# wordclock_v1_8.net
KiCad netlist of a schematic drawn in EAGLE
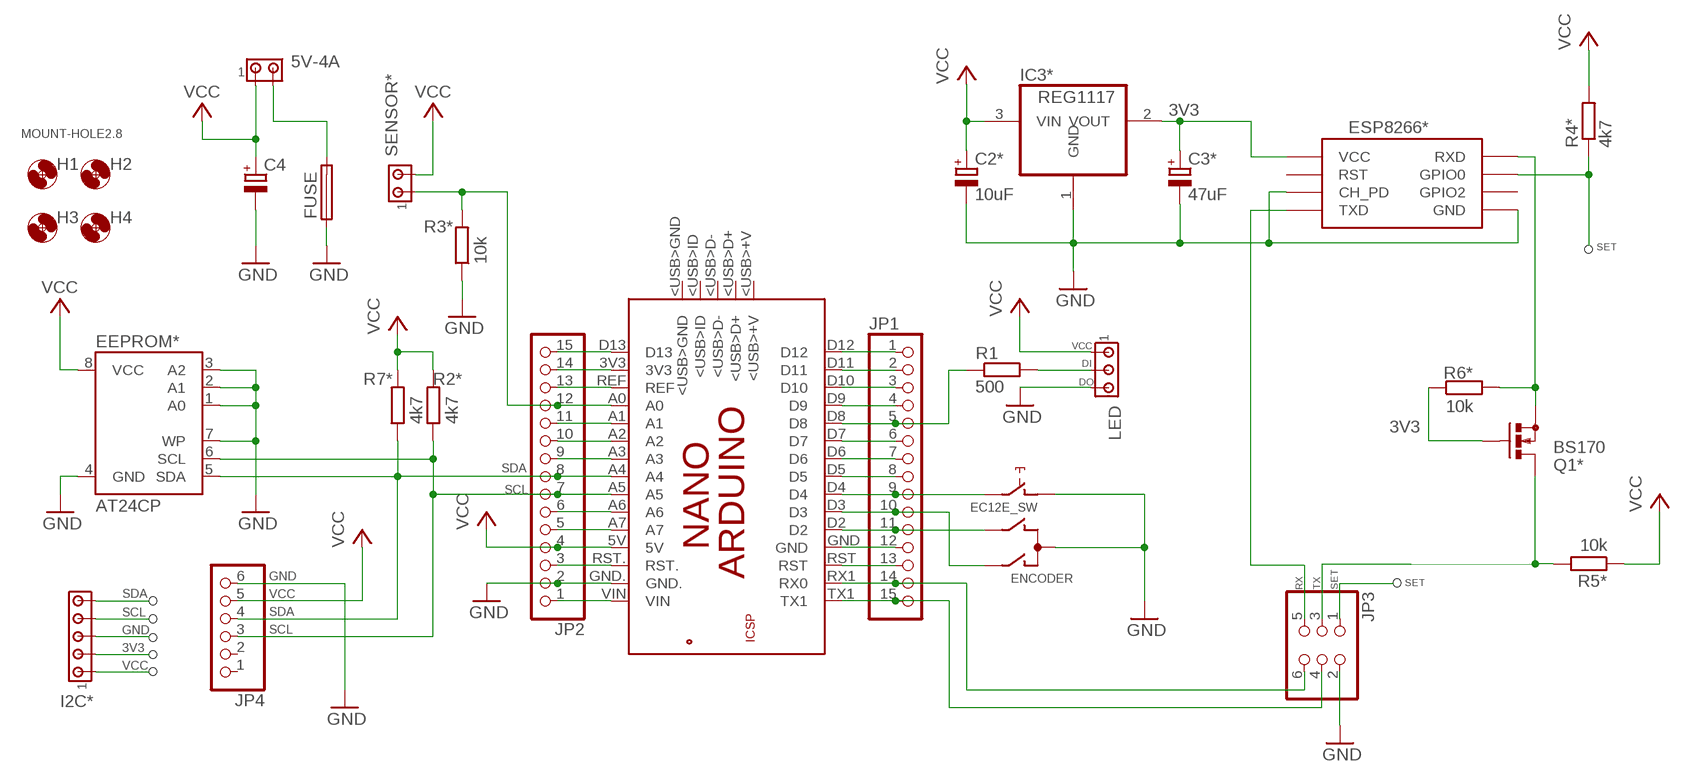
[diagram p0: schematic, sheet 1]

(export (version "E")
  (design (tool "Eeschema 10.0.6"))
  (components
    (comp (ref "5V-4A")
      (value "5V-4A")
      (footprint "eagle-import:1X2MTA")
      (libsource (lib "eagle-import") (part "MTA02-156"))
    )
    (comp (ref "C2*")
      (value "10uF")
      (footprint "eagle-import:B45181A")
      (libsource (lib "eagle-import") (part "CPOL-EUB45181A"))
    )
    (comp (ref "C3*")
      (value "47uF")
      (footprint "eagle-import:B45181A")
      (libsource (lib "eagle-import") (part "CPOL-EUB45181A"))
    )
    (comp (ref "C4")
      (value "CPOL-EUE5-10.5")
      (footprint "eagle-import:E5-10,5")
      (libsource (lib "eagle-import") (part "CPOL-EUE5-10.5"))
    )
    (comp (ref "EEPROM*")
      (value "AT24CP")
      (footprint "eagle-import:DIL08")
      (fields (field (name "MPN") "AT24C1024BW-SH-B"))
      (libsource (lib "eagle-import") (part "AT24CP"))
    )
    (comp (ref "ENCODER")
      (value "EC12E_SW")
      (footprint "eagle-import:ALPS_EC12E_SW")
      (fields (field (name "MPN") "EC12E2424407"))
      (libsource (lib "eagle-import") (part "EC12E_SW"))
    )
    (comp (ref "ESP8266*")
      (value "ESP01")
      (footprint "eagle-import:ESP01")
      (libsource (lib "eagle-import") (part "ESP01"))
    )
    (comp (ref "FUSE")
      (value "FUSELITTLEFUSE")
      (footprint "eagle-import:LITTLEFUSE")
      (libsource (lib "eagle-import") (part "FUSELITTLEFUSE"))
    )
    (comp (ref "H1")
      (value "MOUNT-HOLE2.8")
      (footprint "eagle-import:2,8")
      (libsource (lib "eagle-import") (part "MOUNT-HOLE2.8"))
    )
    (comp (ref "H2")
      (value "MOUNT-HOLE2.8")
      (footprint "eagle-import:2,8")
      (libsource (lib "eagle-import") (part "MOUNT-HOLE2.8"))
    )
    (comp (ref "H3")
      (value "MOUNT-HOLE2.8")
      (footprint "eagle-import:2,8")
      (libsource (lib "eagle-import") (part "MOUNT-HOLE2.8"))
    )
    (comp (ref "H4")
      (value "MOUNT-HOLE2.8")
      (footprint "eagle-import:2,8")
      (libsource (lib "eagle-import") (part "MOUNT-HOLE2.8"))
    )
    (comp (ref "I2C*")
      (value "MTA05-100")
      (footprint "eagle-import:10X05MTA")
      (libsource (lib "eagle-import") (part "MTA05-100"))
    )
    (comp (ref "IC3*")
      (value "REG1117")
      (footprint "eagle-import:SOT223")
      (libsource (lib "eagle-import") (part "REG1117"))
    )
    (comp (ref "JP1")
      (value "PINHD-1X15")
      (footprint "eagle-import:1X15")
      (libsource (lib "eagle-import") (part "PINHD-1X15"))
    )
    (comp (ref "JP2")
      (value "PINHD-1X15")
      (footprint "eagle-import:1X15")
      (libsource (lib "eagle-import") (part "PINHD-1X15"))
    )
    (comp (ref "JP3")
      (value "PINHD-2X3")
      (footprint "eagle-import:2X03")
      (libsource (lib "eagle-import") (part "PINHD-2X3"))
    )
    (comp (ref "JP4")
      (value "PINHD-1X6")
      (footprint "eagle-import:1X06")
      (libsource (lib "eagle-import") (part "PINHD-1X6"))
    )
    (comp (ref "LED")
      (value "MTA03-156")
      (footprint "eagle-import:1X3MTA")
      (libsource (lib "eagle-import") (part "MTA03-156"))
    )
    (comp (ref "PCB2")
      (value "ARDUINO_NANO")
      (footprint "eagle-import:ARDUINO_NANO")
      (libsource (lib "eagle-import") (part "ARDUINO_NANO"))
    )
    (comp (ref "Q1*")
      (value "BS170")
      (footprint "eagle-import:SOT54E")
      (libsource (lib "eagle-import") (part "BS170"))
    )
    (comp (ref "R1")
      (value "500")
      (footprint "eagle-import:0207_7")
      (libsource (lib "eagle-import") (part "resistor_R-EU_0207/7"))
    )
    (comp (ref "R2*")
      (value "4k7")
      (footprint "eagle-import:0207_10")
      (libsource (lib "eagle-import") (part "R-EU_0207/10"))
    )
    (comp (ref "R3*")
      (value "10k")
      (footprint "eagle-import:0207_10")
      (libsource (lib "eagle-import") (part "R-EU_0207/10"))
    )
    (comp (ref "R4*")
      (value "4k7")
      (footprint "eagle-import:0207_10")
      (libsource (lib "eagle-import") (part "R-EU_0207/10"))
    )
    (comp (ref "R5*")
      (value "10k")
      (footprint "eagle-import:0207_10")
      (libsource (lib "eagle-import") (part "R-EU_0207/10"))
    )
    (comp (ref "R6*")
      (value "10k")
      (footprint "eagle-import:0207_10")
      (libsource (lib "eagle-import") (part "R-EU_0207/10"))
    )
    (comp (ref "R7*")
      (value "4k7")
      (footprint "eagle-import:0207_10")
      (libsource (lib "eagle-import") (part "R-EU_0207/10"))
    )
    (comp (ref "SENSOR*")
      (value "MTA02-156")
      (footprint "eagle-import:1X2MTA")
      (libsource (lib "eagle-import") (part "MTA02-156"))
    )
  )
  (nets
    (net (code "1") (name "3V3") (class "Default")
      (node (ref "C3*") (pin "+") (pinfunction "+_+") (pintype "passive"))
      (node (ref "ESP8266*") (pin "VCC") (pinfunction "VCC_VCC") (pintype "bidirectional"))
      (node (ref "I2C*") (pin "2") (pinfunction "2_2") (pintype "passive"))
      (node (ref "IC3*") (pin "2") (pinfunction "VOUT_2") (pintype "output"))
      (node (ref "Q1*") (pin "G") (pinfunction "G_G") (pintype "passive"))
      (node (ref "R6*") (pin "1") (pinfunction "1_1") (pintype "passive"))
    )
    (net (code "2") (name "DI") (class "Default")
      (node (ref "LED") (pin "2") (pinfunction "2_2") (pintype "passive"))
      (node (ref "R1") (pin "2") (pinfunction "2_2") (pintype "passive"))
    )
    (net (code "3") (name "GND") (class "Default")
      (node (ref "C2*") (pin "-") (pinfunction "-_-") (pintype "passive"))
      (node (ref "C3*") (pin "-") (pinfunction "-_-") (pintype "passive"))
      (node (ref "C4") (pin "-") (pinfunction "-_-") (pintype "passive"))
      (node (ref "EEPROM*") (pin "1") (pinfunction "A0_1") (pintype "input"))
      (node (ref "EEPROM*") (pin "2") (pinfunction "A1_2") (pintype "input"))
      (node (ref "EEPROM*") (pin "3") (pinfunction "A2_3") (pintype "input"))
      (node (ref "EEPROM*") (pin "4") (pinfunction "GND_4") (pintype "power_in"))
      (node (ref "EEPROM*") (pin "7") (pinfunction "WP_7") (pintype "input"))
      (node (ref "ENCODER") (pin "C") (pinfunction "C_C") (pintype "passive"))
      (node (ref "ENCODER") (pin "D") (pinfunction "1_D") (pintype "passive"))
      (node (ref "ESP8266*") (pin "CH_PD") (pinfunction "CH_PD_CH_PD") (pintype "bidirectional"))
      (node (ref "ESP8266*") (pin "GND") (pinfunction "GND_GND") (pintype "bidirectional"))
      (node (ref "FUSE") (pin "1") (pinfunction "1_1") (pintype "passive"))
      (node (ref "I2C*") (pin "3") (pinfunction "3_3") (pintype "passive"))
      (node (ref "IC3*") (pin "1") (pinfunction "GND_1") (pintype "power_in"))
      (node (ref "JP2") (pin "2") (pinfunction "2_2") (pintype "passive"))
      (node (ref "JP3") (pin "2") (pinfunction "2_2") (pintype "passive"))
      (node (ref "JP4") (pin "6") (pinfunction "6_6") (pintype "passive"))
      (node (ref "LED") (pin "3") (pinfunction "3_3") (pintype "passive"))
      (node (ref "PCB2") (pin "GND.") (pinfunction "GND._GND.") (pintype "bidirectional"))
      (node (ref "R3*") (pin "1") (pinfunction "1_1") (pintype "passive"))
    )
    (net (code "4") (name "Net-(5V-4A-Pad2)") (class "Default")
      (node (ref "5V-4A") (pin "2") (pinfunction "2_2") (pintype "passive"))
      (node (ref "FUSE") (pin "2") (pinfunction "2_2") (pintype "passive"))
    )
    (net (code "5") (name "Net-(ENCODER-PadA)") (class "Default")
      (node (ref "ENCODER") (pin "A") (pinfunction "A_A") (pintype "passive"))
      (node (ref "JP1") (pin "10") (pinfunction "10_10") (pintype "passive"))
      (node (ref "PCB2") (pin "D3") (pinfunction "D3_D3") (pintype "bidirectional"))
    )
    (net (code "6") (name "Net-(ENCODER-PadB)") (class "Default")
      (node (ref "ENCODER") (pin "B") (pinfunction "B_B") (pintype "passive"))
      (node (ref "JP1") (pin "11") (pinfunction "11_11") (pintype "passive"))
      (node (ref "PCB2") (pin "D2") (pinfunction "D2_D2") (pintype "bidirectional"))
    )
    (net (code "7") (name "Net-(ENCODERB-2)") (class "Default")
      (node (ref "ENCODER") (pin "E") (pinfunction "2_E") (pintype "passive"))
      (node (ref "JP1") (pin "9") (pinfunction "9_9") (pintype "passive"))
      (node (ref "PCB2") (pin "D4") (pinfunction "D4_D4") (pintype "bidirectional"))
    )
    (net (code "8") (name "Net-(ESP8266*-RXD)") (class "Default")
      (node (ref "ESP8266*") (pin "RX") (pinfunction "RXD_RX") (pintype "bidirectional"))
      (node (ref "Q1*") (pin "S") (pinfunction "S_S") (pintype "passive"))
      (node (ref "R6*") (pin "2") (pinfunction "2_2") (pintype "passive"))
    )
    (net (code "9") (name "Net-(JP1-Pad1)") (class "Default")
      (node (ref "JP1") (pin "1") (pinfunction "1_1") (pintype "passive"))
      (node (ref "PCB2") (pin "D12") (pinfunction "D12_D12") (pintype "bidirectional"))
    )
    (net (code "10") (name "Net-(JP1-Pad2)") (class "Default")
      (node (ref "JP1") (pin "2") (pinfunction "2_2") (pintype "passive"))
      (node (ref "PCB2") (pin "D11") (pinfunction "D11_D11") (pintype "bidirectional"))
    )
    (net (code "11") (name "Net-(JP1-Pad3)") (class "Default")
      (node (ref "JP1") (pin "3") (pinfunction "3_3") (pintype "passive"))
      (node (ref "PCB2") (pin "D10") (pinfunction "D10_D10") (pintype "bidirectional"))
    )
    (net (code "12") (name "Net-(JP1-Pad4)") (class "Default")
      (node (ref "JP1") (pin "4") (pinfunction "4_4") (pintype "passive"))
      (node (ref "PCB2") (pin "D9") (pinfunction "D9_D9") (pintype "bidirectional"))
    )
    (net (code "13") (name "Net-(JP1-Pad5)") (class "Default")
      (node (ref "JP1") (pin "5") (pinfunction "5_5") (pintype "passive"))
      (node (ref "PCB2") (pin "D8") (pinfunction "D8_D8") (pintype "bidirectional"))
      (node (ref "R1") (pin "1") (pinfunction "1_1") (pintype "passive"))
    )
    (net (code "14") (name "Net-(JP1-Pad6)") (class "Default")
      (node (ref "JP1") (pin "6") (pinfunction "6_6") (pintype "passive"))
      (node (ref "PCB2") (pin "D7") (pinfunction "D7_D7") (pintype "bidirectional"))
    )
    (net (code "15") (name "Net-(JP1-Pad7)") (class "Default")
      (node (ref "JP1") (pin "7") (pinfunction "7_7") (pintype "passive"))
      (node (ref "PCB2") (pin "D6") (pinfunction "D6_D6") (pintype "bidirectional"))
    )
    (net (code "16") (name "Net-(JP1-Pad8)") (class "Default")
      (node (ref "JP1") (pin "8") (pinfunction "8_8") (pintype "passive"))
      (node (ref "PCB2") (pin "D5") (pinfunction "D5_D5") (pintype "bidirectional"))
    )
    (net (code "17") (name "Net-(JP1-Pad12)") (class "Default")
      (node (ref "JP1") (pin "12") (pinfunction "12_12") (pintype "passive"))
      (node (ref "PCB2") (pin "GND") (pinfunction "GND_GND") (pintype "bidirectional"))
    )
    (net (code "18") (name "Net-(JP1-Pad13)") (class "Default")
      (node (ref "JP1") (pin "13") (pinfunction "13_13") (pintype "passive"))
      (node (ref "PCB2") (pin "RST") (pinfunction "RST_RST") (pintype "bidirectional"))
    )
    (net (code "19") (name "Net-(JP1-Pad15)") (class "Default")
      (node (ref "JP1") (pin "15") (pinfunction "15_15") (pintype "passive"))
      (node (ref "JP3") (pin "4") (pinfunction "4_4") (pintype "passive"))
      (node (ref "PCB2") (pin "TX1") (pinfunction "TX1_TX1") (pintype "bidirectional"))
    )
    (net (code "20") (name "Net-(JP2-Pad1)") (class "Default")
      (node (ref "JP2") (pin "1") (pinfunction "1_1") (pintype "passive"))
      (node (ref "PCB2") (pin "VIN") (pinfunction "VIN_VIN") (pintype "bidirectional"))
    )
    (net (code "21") (name "Net-(JP2-Pad3)") (class "Default")
      (node (ref "JP2") (pin "3") (pinfunction "3_3") (pintype "passive"))
      (node (ref "PCB2") (pin "RST.") (pinfunction "RST._RST.") (pintype "bidirectional"))
    )
    (net (code "22") (name "Net-(JP2-Pad5)") (class "Default")
      (node (ref "JP2") (pin "5") (pinfunction "5_5") (pintype "passive"))
      (node (ref "PCB2") (pin "A7") (pinfunction "A7_A7") (pintype "bidirectional"))
    )
    (net (code "23") (name "Net-(JP2-Pad6)") (class "Default")
      (node (ref "JP2") (pin "6") (pinfunction "6_6") (pintype "passive"))
      (node (ref "PCB2") (pin "A6") (pinfunction "A6_A6") (pintype "bidirectional"))
    )
    (net (code "24") (name "Net-(JP2-Pad9)") (class "Default")
      (node (ref "JP2") (pin "9") (pinfunction "9_9") (pintype "passive"))
      (node (ref "PCB2") (pin "A3") (pinfunction "A3_A3") (pintype "bidirectional"))
    )
    (net (code "25") (name "Net-(JP2-Pad10)") (class "Default")
      (node (ref "JP2") (pin "10") (pinfunction "10_10") (pintype "passive"))
      (node (ref "PCB2") (pin "A2") (pinfunction "A2_A2") (pintype "bidirectional"))
    )
    (net (code "26") (name "Net-(JP2-Pad11)") (class "Default")
      (node (ref "JP2") (pin "11") (pinfunction "11_11") (pintype "passive"))
      (node (ref "PCB2") (pin "A1") (pinfunction "A1_A1") (pintype "bidirectional"))
    )
    (net (code "27") (name "Net-(JP2-Pad12)") (class "Default")
      (node (ref "JP2") (pin "12") (pinfunction "12_12") (pintype "passive"))
      (node (ref "PCB2") (pin "A0") (pinfunction "A0_A0") (pintype "bidirectional"))
      (node (ref "R3*") (pin "2") (pinfunction "2_2") (pintype "passive"))
      (node (ref "SENSOR*") (pin "1") (pinfunction "1_1") (pintype "passive"))
    )
    (net (code "28") (name "Net-(JP2-Pad13)") (class "Default")
      (node (ref "JP2") (pin "13") (pinfunction "13_13") (pintype "passive"))
      (node (ref "PCB2") (pin "REF") (pinfunction "REF_REF") (pintype "bidirectional"))
    )
    (net (code "29") (name "Net-(JP2-Pad14)") (class "Default")
      (node (ref "JP2") (pin "14") (pinfunction "14_14") (pintype "passive"))
      (node (ref "PCB2") (pin "3V3") (pinfunction "3V3_3V3") (pintype "bidirectional"))
    )
    (net (code "30") (name "Net-(JP2-Pad15)") (class "Default")
      (node (ref "JP2") (pin "15") (pinfunction "15_15") (pintype "passive"))
      (node (ref "PCB2") (pin "D13") (pinfunction "D13_D13") (pintype "bidirectional"))
    )
    (net (code "31") (name "Net-(PCB2-RX0)") (class "Default")
      (node (ref "JP1") (pin "14") (pinfunction "14_14") (pintype "passive"))
      (node (ref "JP3") (pin "6") (pinfunction "6_6") (pintype "passive"))
      (node (ref "PCB2") (pin "RX1") (pinfunction "RX0_RX1") (pintype "bidirectional"))
    )
    (net (code "32") (name "RX") (class "Default")
      (node (ref "ESP8266*") (pin "TX") (pinfunction "TXD_TX") (pintype "bidirectional"))
      (node (ref "JP3") (pin "5") (pinfunction "5_5") (pintype "passive"))
    )
    (net (code "33") (name "SCL") (class "Default")
      (node (ref "EEPROM*") (pin "6") (pinfunction "SCL_6") (pintype "bidirectional"))
      (node (ref "I2C*") (pin "4") (pinfunction "4_4") (pintype "passive"))
      (node (ref "JP2") (pin "7") (pinfunction "7_7") (pintype "passive"))
      (node (ref "JP4") (pin "3") (pinfunction "3_3") (pintype "passive"))
      (node (ref "PCB2") (pin "A5") (pinfunction "A5_A5") (pintype "bidirectional"))
      (node (ref "R2*") (pin "1") (pinfunction "1_1") (pintype "passive"))
    )
    (net (code "34") (name "SDA") (class "Default")
      (node (ref "EEPROM*") (pin "5") (pinfunction "SDA_5") (pintype "bidirectional"))
      (node (ref "I2C*") (pin "5") (pinfunction "5_5") (pintype "passive"))
      (node (ref "JP2") (pin "8") (pinfunction "8_8") (pintype "passive"))
      (node (ref "JP4") (pin "4") (pinfunction "4_4") (pintype "passive"))
      (node (ref "PCB2") (pin "A4") (pinfunction "A4_A4") (pintype "bidirectional"))
      (node (ref "R7*") (pin "1") (pinfunction "1_1") (pintype "passive"))
    )
    (net (code "35") (name "SET") (class "Default")
      (node (ref "ESP8266*") (pin "GPIO0") (pinfunction "GPIO0_GPIO0") (pintype "bidirectional"))
      (node (ref "JP3") (pin "1") (pinfunction "1_1") (pintype "passive"))
      (node (ref "R4*") (pin "1") (pinfunction "1_1") (pintype "passive"))
    )
    (net (code "36") (name "TX") (class "Default")
      (node (ref "JP3") (pin "3") (pinfunction "3_3") (pintype "passive"))
      (node (ref "Q1*") (pin "D") (pinfunction "D_D") (pintype "passive"))
      (node (ref "R5*") (pin "2") (pinfunction "2_2") (pintype "passive"))
    )
    (net (code "37") (name "VCC") (class "Default")
      (node (ref "5V-4A") (pin "1") (pinfunction "1_1") (pintype "passive"))
      (node (ref "C2*") (pin "+") (pinfunction "+_+") (pintype "passive"))
      (node (ref "C4") (pin "+") (pinfunction "+_+") (pintype "passive"))
      (node (ref "EEPROM*") (pin "8") (pinfunction "VCC_8") (pintype "power_in"))
      (node (ref "I2C*") (pin "1") (pinfunction "1_1") (pintype "passive"))
      (node (ref "IC3*") (pin "3") (pinfunction "VIN_3") (pintype "input"))
      (node (ref "JP2") (pin "4") (pinfunction "4_4") (pintype "passive"))
      (node (ref "JP4") (pin "5") (pinfunction "5_5") (pintype "passive"))
      (node (ref "LED") (pin "1") (pinfunction "1_1") (pintype "passive"))
      (node (ref "PCB2") (pin "5V") (pinfunction "5V_5V") (pintype "bidirectional"))
      (node (ref "R2*") (pin "2") (pinfunction "2_2") (pintype "passive"))
      (node (ref "R4*") (pin "2") (pinfunction "2_2") (pintype "passive"))
      (node (ref "R5*") (pin "1") (pinfunction "1_1") (pintype "passive"))
      (node (ref "R7*") (pin "2") (pinfunction "2_2") (pintype "passive"))
      (node (ref "SENSOR*") (pin "2") (pinfunction "2_2") (pintype "passive"))
    )
    (net (code "38") (name "unconnected-(ESP8266*-PadGPIO2)") (class "Default")
      (node (ref "ESP8266*") (pin "GPIO2") (pinfunction "GPIO2_GPIO2") (pintype "bidirectional"))
    )
    (net (code "39") (name "unconnected-(ESP8266*-PadRST)") (class "Default")
      (node (ref "ESP8266*") (pin "RST") (pinfunction "RST_RST") (pintype "bidirectional"))
    )
    (net (code "40") (name "unconnected-(JP4-Pad1)") (class "Default")
      (node (ref "JP4") (pin "1") (pinfunction "1_1") (pintype "passive"))
    )
    (net (code "41") (name "unconnected-(JP4-Pad2)") (class "Default")
      (node (ref "JP4") (pin "2") (pinfunction "2_2") (pintype "passive"))
    )
    (net (code "42") (name "unconnected-(PCB2-Pad5V.)") (class "Default")
      (node (ref "PCB2") (pin "5V.") (pinfunction "5V._5V.") (pintype "bidirectional"))
    )
    (net (code "43") (name "unconnected-(PCB2-Pad<USB>+V)") (class "Default")
      (node (ref "PCB2") (pin "<USB>+V") (pinfunction "<USB>+V_<USB>+V") (pintype "bidirectional"))
    )
    (net (code "44") (name "unconnected-(PCB2-Pad<USB>D+)") (class "Default")
      (node (ref "PCB2") (pin "<USB>D+") (pinfunction "<USB>D+_<USB>D+") (pintype "bidirectional"))
    )
    (net (code "45") (name "unconnected-(PCB2-Pad<USB>D-)") (class "Default")
      (node (ref "PCB2") (pin "<USB>D-") (pinfunction "<USB>D-_<USB>D-") (pintype "bidirectional"))
    )
    (net (code "46") (name "unconnected-(PCB2-Pad<USB>GND)") (class "Default")
      (node (ref "PCB2") (pin "<USB>GND") (pinfunction "<USB>GND_<USB>GND") (pintype "bidirectional"))
    )
    (net (code "47") (name "unconnected-(PCB2-Pad<USB>ID)") (class "Default")
      (node (ref "PCB2") (pin "<USB>ID") (pinfunction "<USB>ID_<USB>ID") (pintype "bidirectional"))
    )
    (net (code "48") (name "unconnected-(PCB2-PadGND_)") (class "Default")
      (node (ref "PCB2") (pin "GND_") (pinfunction "GND__GND_") (pintype "bidirectional"))
    )
    (net (code "49") (name "unconnected-(PCB2-PadMISO)") (class "Default")
      (node (ref "PCB2") (pin "MISO") (pinfunction "MISO_MISO") (pintype "bidirectional"))
    )
    (net (code "50") (name "unconnected-(PCB2-PadMOSI)") (class "Default")
      (node (ref "PCB2") (pin "MOSI") (pinfunction "MOSI_MOSI") (pintype "bidirectional"))
    )
    (net (code "51") (name "unconnected-(PCB2-PadRESET..)") (class "Default")
      (node (ref "PCB2") (pin "RESET..") (pinfunction "RESET.._RESET..") (pintype "bidirectional"))
    )
    (net (code "52") (name "unconnected-(PCB2-PadSCK)") (class "Default")
      (node (ref "PCB2") (pin "SCK") (pinfunction "SCK_SCK") (pintype "bidirectional"))
    )
  )
)
